# BumpSensors.net
KiCad netlist of a schematic drawn in Altium Designer
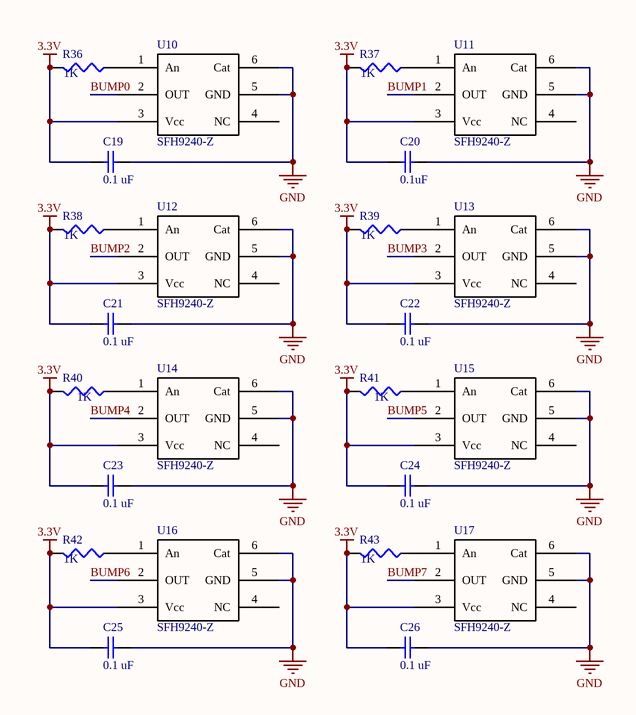
[diagram p0: BumpSensors.SchDoc]

(export (version "E")
  (design (tool "Eeschema 10.0.6"))
  (components
    (comp (ref "C19")
      (value "0.1 uF")
      (footprint "CAPC1005L")
      (description "Capacitor (Semiconductor SIM Model)")
      (fields (field (name "Comment") "Cap Semi") (field (name "PUBLISHER") "Altium Limited"))
      (libsource (lib "Miscellaneous Devices") (part "Cap Semi"))
    )
    (comp (ref "C20")
      (value "0.1uF")
      (footprint "CAPC1005L")
      (description "Capacitor (Semiconductor SIM Model)")
      (fields (field (name "Comment") "Cap Semi") (field (name "PUBLISHER") "Altium Limited"))
      (libsource (lib "Miscellaneous Devices") (part "Cap Semi"))
    )
    (comp (ref "C21")
      (value "0.1 uF")
      (footprint "CAPC1005L")
      (description "Capacitor (Semiconductor SIM Model)")
      (fields (field (name "Comment") "Cap Semi") (field (name "PUBLISHER") "Altium Limited"))
      (libsource (lib "Miscellaneous Devices") (part "Cap Semi"))
    )
    (comp (ref "C22")
      (value "0.1 uF")
      (footprint "CAPC1005L")
      (description "Capacitor (Semiconductor SIM Model)")
      (fields (field (name "Comment") "Cap Semi") (field (name "PUBLISHER") "Altium Limited"))
      (libsource (lib "Miscellaneous Devices") (part "Cap Semi"))
    )
    (comp (ref "C23")
      (value "0.1 uF")
      (footprint "CAPC1005L")
      (description "Capacitor (Semiconductor SIM Model)")
      (fields (field (name "Comment") "Cap Semi") (field (name "PUBLISHER") "Altium Limited"))
      (libsource (lib "Miscellaneous Devices") (part "Cap Semi"))
    )
    (comp (ref "C24")
      (value "0.1 uF")
      (footprint "CAPC1005L")
      (description "Capacitor (Semiconductor SIM Model)")
      (fields (field (name "Comment") "Cap Semi") (field (name "PUBLISHER") "Altium Limited"))
      (libsource (lib "Miscellaneous Devices") (part "Cap Semi"))
    )
    (comp (ref "C25")
      (value "0.1 uF")
      (footprint "CAPC1005L")
      (description "Capacitor (Semiconductor SIM Model)")
      (fields (field (name "Comment") "Cap Semi") (field (name "PUBLISHER") "Altium Limited"))
      (libsource (lib "Miscellaneous Devices") (part "Cap Semi"))
    )
    (comp (ref "C26")
      (value "0.1 uF")
      (footprint "CAPC1005L")
      (description "Capacitor (Semiconductor SIM Model)")
      (fields (field (name "Comment") "Cap Semi") (field (name "PUBLISHER") "Altium Limited"))
      (libsource (lib "Miscellaneous Devices") (part "Cap Semi"))
    )
    (comp (ref "R36")
      (value "1K")
      (footprint "RESC1608L")
      (description "Resistor")
      (fields (field (name "Comment") "Res3") (field (name "PUBLISHER") "Altium Limited"))
      (libsource (lib "Miscellaneous Devices") (part "Res3"))
    )
    (comp (ref "R37")
      (value "1K")
      (footprint "RESC1608L")
      (description "Resistor")
      (fields (field (name "Comment") "Res3") (field (name "PUBLISHER") "Altium Limited"))
      (libsource (lib "Miscellaneous Devices") (part "Res3"))
    )
    (comp (ref "R38")
      (value "1K")
      (footprint "RESC1608L")
      (description "Resistor")
      (fields (field (name "Comment") "Res3") (field (name "PUBLISHER") "Altium Limited"))
      (libsource (lib "Miscellaneous Devices") (part "Res3"))
    )
    (comp (ref "R39")
      (value "1K")
      (footprint "RESC1608L")
      (description "Resistor")
      (fields (field (name "Comment") "Res3") (field (name "PUBLISHER") "Altium Limited"))
      (libsource (lib "Miscellaneous Devices") (part "Res3"))
    )
    (comp (ref "R40")
      (value "1K")
      (footprint "RESC1608L")
      (description "Resistor")
      (fields (field (name "Comment") "Res3") (field (name "PUBLISHER") "Altium Limited"))
      (libsource (lib "Miscellaneous Devices") (part "Res3"))
    )
    (comp (ref "R41")
      (value "1K")
      (footprint "RESC1608L")
      (description "Resistor")
      (fields (field (name "Comment") "Res3") (field (name "PUBLISHER") "Altium Limited"))
      (libsource (lib "Miscellaneous Devices") (part "Res3"))
    )
    (comp (ref "R42")
      (value "1K")
      (footprint "RESC1608L")
      (description "Resistor")
      (fields (field (name "Comment") "Res3") (field (name "PUBLISHER") "Altium Limited"))
      (libsource (lib "Miscellaneous Devices") (part "Res3"))
    )
    (comp (ref "R43")
      (value "1K")
      (footprint "RESC1608L")
      (description "Resistor")
      (fields (field (name "Comment") "Res3") (field (name "PUBLISHER") "Altium Limited"))
      (libsource (lib "Miscellaneous Devices") (part "Res3"))
    )
    (comp (ref "U10")
      (value "SFH9240-Z")
      (footprint "SFH9240-Z")
      (libsource (lib "mrone") (part "SFH9240-Z"))
    )
    (comp (ref "U11")
      (value "SFH9240-Z")
      (footprint "SFH9240-Z")
      (libsource (lib "mrone") (part "SFH9240-Z"))
    )
    (comp (ref "U12")
      (value "SFH9240-Z")
      (footprint "SFH9240-Z")
      (libsource (lib "mrone") (part "SFH9240-Z"))
    )
    (comp (ref "U13")
      (value "SFH9240-Z")
      (footprint "SFH9240-Z")
      (libsource (lib "mrone") (part "SFH9240-Z"))
    )
    (comp (ref "U14")
      (value "SFH9240-Z")
      (footprint "SFH9240-Z")
      (libsource (lib "mrone") (part "SFH9240-Z"))
    )
    (comp (ref "U15")
      (value "SFH9240-Z")
      (footprint "SFH9240-Z")
      (libsource (lib "mrone") (part "SFH9240-Z"))
    )
    (comp (ref "U16")
      (value "SFH9240-Z")
      (footprint "SFH9240-Z")
      (libsource (lib "mrone") (part "SFH9240-Z"))
    )
    (comp (ref "U17")
      (value "SFH9240-Z")
      (footprint "SFH9240-Z")
      (libsource (lib "mrone") (part "SFH9240-Z"))
    )
  )
  (nets
    (net (code "1") (name "/BUMP0") (class "Default")
      (node (ref "U10") (pin "2") (pinfunction "OUT_2") (pintype "passive"))
    )
    (net (code "2") (name "/BUMP1") (class "Default")
      (node (ref "U11") (pin "2") (pinfunction "OUT_2") (pintype "passive"))
    )
    (net (code "3") (name "/BUMP2") (class "Default")
      (node (ref "U12") (pin "2") (pinfunction "OUT_2") (pintype "passive"))
    )
    (net (code "4") (name "/BUMP3") (class "Default")
      (node (ref "U13") (pin "2") (pinfunction "OUT_2") (pintype "passive"))
    )
    (net (code "5") (name "/BUMP4") (class "Default")
      (node (ref "U14") (pin "2") (pinfunction "OUT_2") (pintype "passive"))
    )
    (net (code "6") (name "/BUMP5") (class "Default")
      (node (ref "U15") (pin "2") (pinfunction "OUT_2") (pintype "passive"))
    )
    (net (code "7") (name "/BUMP6") (class "Default")
      (node (ref "U16") (pin "2") (pinfunction "OUT_2") (pintype "passive"))
    )
    (net (code "8") (name "/BUMP7") (class "Default")
      (node (ref "U17") (pin "2") (pinfunction "OUT_2") (pintype "passive"))
    )
    (net (code "9") (name "3.3V") (class "Default")
      (node (ref "C19") (pin "2") (pinfunction "2_2") (pintype "passive"))
      (node (ref "C20") (pin "2") (pinfunction "2_2") (pintype "passive"))
      (node (ref "C21") (pin "2") (pinfunction "2_2") (pintype "passive"))
      (node (ref "C22") (pin "2") (pinfunction "2_2") (pintype "passive"))
      (node (ref "C23") (pin "2") (pinfunction "2_2") (pintype "passive"))
      (node (ref "C24") (pin "2") (pinfunction "2_2") (pintype "passive"))
      (node (ref "C25") (pin "2") (pinfunction "2_2") (pintype "passive"))
      (node (ref "C26") (pin "2") (pinfunction "2_2") (pintype "passive"))
      (node (ref "R36") (pin "2") (pinfunction "2_2") (pintype "passive"))
      (node (ref "R37") (pin "2") (pinfunction "2_2") (pintype "passive"))
      (node (ref "R38") (pin "2") (pinfunction "2_2") (pintype "passive"))
      (node (ref "R39") (pin "2") (pinfunction "2_2") (pintype "passive"))
      (node (ref "R40") (pin "2") (pinfunction "2_2") (pintype "passive"))
      (node (ref "R41") (pin "2") (pinfunction "2_2") (pintype "passive"))
      (node (ref "R42") (pin "2") (pinfunction "2_2") (pintype "passive"))
      (node (ref "R43") (pin "2") (pinfunction "2_2") (pintype "passive"))
      (node (ref "U10") (pin "3") (pinfunction "Vcc_3") (pintype "passive"))
      (node (ref "U11") (pin "3") (pinfunction "Vcc_3") (pintype "passive"))
      (node (ref "U12") (pin "3") (pinfunction "Vcc_3") (pintype "passive"))
      (node (ref "U13") (pin "3") (pinfunction "Vcc_3") (pintype "passive"))
      (node (ref "U14") (pin "3") (pinfunction "Vcc_3") (pintype "passive"))
      (node (ref "U15") (pin "3") (pinfunction "Vcc_3") (pintype "passive"))
      (node (ref "U16") (pin "3") (pinfunction "Vcc_3") (pintype "passive"))
      (node (ref "U17") (pin "3") (pinfunction "Vcc_3") (pintype "passive"))
    )
    (net (code "10") (name "GND") (class "Default")
      (node (ref "C19") (pin "1") (pinfunction "1_1") (pintype "passive"))
      (node (ref "C20") (pin "1") (pinfunction "1_1") (pintype "passive"))
      (node (ref "C21") (pin "1") (pinfunction "1_1") (pintype "passive"))
      (node (ref "C22") (pin "1") (pinfunction "1_1") (pintype "passive"))
      (node (ref "C23") (pin "1") (pinfunction "1_1") (pintype "passive"))
      (node (ref "C24") (pin "1") (pinfunction "1_1") (pintype "passive"))
      (node (ref "C25") (pin "1") (pinfunction "1_1") (pintype "passive"))
      (node (ref "C26") (pin "1") (pinfunction "1_1") (pintype "passive"))
      (node (ref "U10") (pin "5") (pinfunction "GND_5") (pintype "passive"))
      (node (ref "U10") (pin "6") (pinfunction "Cat_6") (pintype "passive"))
      (node (ref "U11") (pin "5") (pinfunction "GND_5") (pintype "passive"))
      (node (ref "U11") (pin "6") (pinfunction "Cat_6") (pintype "passive"))
      (node (ref "U12") (pin "5") (pinfunction "GND_5") (pintype "passive"))
      (node (ref "U12") (pin "6") (pinfunction "Cat_6") (pintype "passive"))
      (node (ref "U13") (pin "5") (pinfunction "GND_5") (pintype "passive"))
      (node (ref "U13") (pin "6") (pinfunction "Cat_6") (pintype "passive"))
      (node (ref "U14") (pin "5") (pinfunction "GND_5") (pintype "passive"))
      (node (ref "U14") (pin "6") (pinfunction "Cat_6") (pintype "passive"))
      (node (ref "U15") (pin "5") (pinfunction "GND_5") (pintype "passive"))
      (node (ref "U15") (pin "6") (pinfunction "Cat_6") (pintype "passive"))
      (node (ref "U16") (pin "5") (pinfunction "GND_5") (pintype "passive"))
      (node (ref "U16") (pin "6") (pinfunction "Cat_6") (pintype "passive"))
      (node (ref "U17") (pin "5") (pinfunction "GND_5") (pintype "passive"))
      (node (ref "U17") (pin "6") (pinfunction "Cat_6") (pintype "passive"))
    )
    (net (code "11") (name "Net-(U10-An)") (class "Default")
      (node (ref "R36") (pin "1") (pinfunction "1_1") (pintype "passive"))
      (node (ref "U10") (pin "1") (pinfunction "An_1") (pintype "passive"))
    )
    (net (code "12") (name "Net-(U11-An)") (class "Default")
      (node (ref "R37") (pin "1") (pinfunction "1_1") (pintype "passive"))
      (node (ref "U11") (pin "1") (pinfunction "An_1") (pintype "passive"))
    )
    (net (code "13") (name "Net-(U12-An)") (class "Default")
      (node (ref "R38") (pin "1") (pinfunction "1_1") (pintype "passive"))
      (node (ref "U12") (pin "1") (pinfunction "An_1") (pintype "passive"))
    )
    (net (code "14") (name "Net-(U13-An)") (class "Default")
      (node (ref "R39") (pin "1") (pinfunction "1_1") (pintype "passive"))
      (node (ref "U13") (pin "1") (pinfunction "An_1") (pintype "passive"))
    )
    (net (code "15") (name "Net-(U14-An)") (class "Default")
      (node (ref "R40") (pin "1") (pinfunction "1_1") (pintype "passive"))
      (node (ref "U14") (pin "1") (pinfunction "An_1") (pintype "passive"))
    )
    (net (code "16") (name "Net-(U15-An)") (class "Default")
      (node (ref "R41") (pin "1") (pinfunction "1_1") (pintype "passive"))
      (node (ref "U15") (pin "1") (pinfunction "An_1") (pintype "passive"))
    )
    (net (code "17") (name "Net-(U16-An)") (class "Default")
      (node (ref "R42") (pin "1") (pinfunction "1_1") (pintype "passive"))
      (node (ref "U16") (pin "1") (pinfunction "An_1") (pintype "passive"))
    )
    (net (code "18") (name "Net-(U17-An)") (class "Default")
      (node (ref "R43") (pin "1") (pinfunction "1_1") (pintype "passive"))
      (node (ref "U17") (pin "1") (pinfunction "An_1") (pintype "passive"))
    )
    (net (code "19") (name "unconnected-(U10-NC-Pad4)") (class "Default")
      (node (ref "U10") (pin "4") (pinfunction "NC_4") (pintype "passive"))
    )
    (net (code "20") (name "unconnected-(U11-NC-Pad4)") (class "Default")
      (node (ref "U11") (pin "4") (pinfunction "NC_4") (pintype "passive"))
    )
    (net (code "21") (name "unconnected-(U12-NC-Pad4)") (class "Default")
      (node (ref "U12") (pin "4") (pinfunction "NC_4") (pintype "passive"))
    )
    (net (code "22") (name "unconnected-(U13-NC-Pad4)") (class "Default")
      (node (ref "U13") (pin "4") (pinfunction "NC_4") (pintype "passive"))
    )
    (net (code "23") (name "unconnected-(U14-NC-Pad4)") (class "Default")
      (node (ref "U14") (pin "4") (pinfunction "NC_4") (pintype "passive"))
    )
    (net (code "24") (name "unconnected-(U15-NC-Pad4)") (class "Default")
      (node (ref "U15") (pin "4") (pinfunction "NC_4") (pintype "passive"))
    )
    (net (code "25") (name "unconnected-(U16-NC-Pad4)") (class "Default")
      (node (ref "U16") (pin "4") (pinfunction "NC_4") (pintype "passive"))
    )
    (net (code "26") (name "unconnected-(U17-NC-Pad4)") (class "Default")
      (node (ref "U17") (pin "4") (pinfunction "NC_4") (pintype "passive"))
    )
  )
)
